# DingDong.net
KiCad netlist of a schematic drawn in Altium Designer
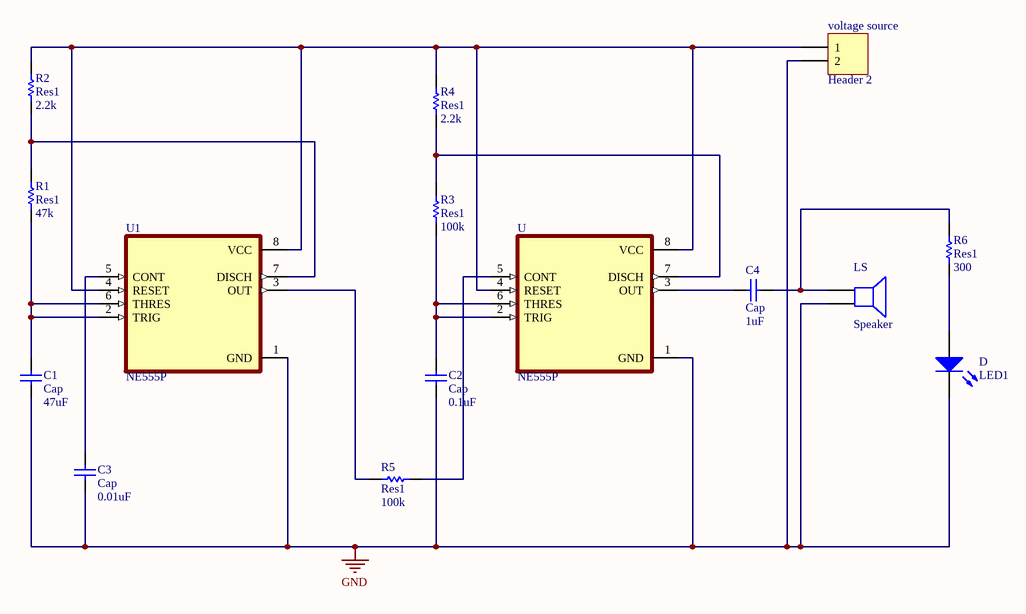
[diagram p0: DingDong.SchDoc]

(export (version "E")
  (design (tool "Eeschema 10.0.6"))
  (components
    (comp (ref "C1")
      (value "Cap")
      (footprint "RAD-0.3")
      (description "Capacitor")
      (fields (field (name "ALTIUM_VALUE") "47uF") (field (name "PUBLISHER") "Altium Limited"))
      (libsource (lib "Miscellaneous Devices") (part "Cap"))
    )
    (comp (ref "C2")
      (value "Cap")
      (footprint "RAD-0.3")
      (description "Capacitor")
      (fields (field (name "ALTIUM_VALUE") "0.1uF") (field (name "PUBLISHER") "Altium Limited"))
      (libsource (lib "Miscellaneous Devices") (part "Cap"))
    )
    (comp (ref "C3")
      (value "Cap")
      (footprint "RAD-0.3")
      (description "Capacitor")
      (fields (field (name "ALTIUM_VALUE") "0.01uF") (field (name "PUBLISHER") "Altium Limited"))
      (libsource (lib "Miscellaneous Devices") (part "Cap"))
    )
    (comp (ref "C4")
      (value "Cap")
      (footprint "RAD-0.3")
      (description "Capacitor")
      (fields (field (name "ALTIUM_VALUE") "1uF") (field (name "PUBLISHER") "Altium Limited"))
      (libsource (lib "Miscellaneous Devices") (part "Cap"))
    )
    (comp (ref "D")
      (value "LED1")
      (footprint "LED-1")
      (description "Typical RED GaAs LED")
      (fields (field (name "PUBLISHER") "Altium Limited"))
      (libsource (lib "Miscellaneous Devices") (part "LED1"))
    )
    (comp (ref "LS")
      (value "Speaker")
      (footprint "PIN2")
      (description "Loudspeaker")
      (fields (field (name "PUBLISHER") "Altium Limited"))
      (libsource (lib "Miscellaneous Devices") (part "Speaker"))
    )
    (comp (ref "R1")
      (value "Res1")
      (footprint "AXIAL-0.3")
      (description "Resistor")
      (fields (field (name "ALTIUM_VALUE") "47k") (field (name "PUBLISHER") "Altium Limited"))
      (libsource (lib "Miscellaneous Devices") (part "Res1"))
    )
    (comp (ref "R2")
      (value "Res1")
      (footprint "AXIAL-0.3")
      (description "Resistor")
      (fields (field (name "ALTIUM_VALUE") "2.2k") (field (name "PUBLISHER") "Altium Limited"))
      (libsource (lib "Miscellaneous Devices") (part "Res1"))
    )
    (comp (ref "R3")
      (value "Res1")
      (footprint "AXIAL-0.3")
      (description "Resistor")
      (fields (field (name "ALTIUM_VALUE") "100k") (field (name "PUBLISHER") "Altium Limited"))
      (libsource (lib "Miscellaneous Devices") (part "Res1"))
    )
    (comp (ref "R4")
      (value "Res1")
      (footprint "AXIAL-0.3")
      (description "Resistor")
      (fields (field (name "ALTIUM_VALUE") "2.2k") (field (name "PUBLISHER") "Altium Limited"))
      (libsource (lib "Miscellaneous Devices") (part "Res1"))
    )
    (comp (ref "R5")
      (value "Res1")
      (footprint "AXIAL-0.3")
      (description "Resistor")
      (fields (field (name "ALTIUM_VALUE") "100k") (field (name "PUBLISHER") "Altium Limited"))
      (libsource (lib "Miscellaneous Devices") (part "Res1"))
    )
    (comp (ref "R6")
      (value "Res1")
      (footprint "AXIAL-0.3")
      (description "Resistor")
      (fields (field (name "ALTIUM_VALUE") "300") (field (name "PUBLISHER") "Altium Limited"))
      (libsource (lib "Miscellaneous Devices") (part "Res1"))
    )
    (comp (ref "U")
      (value "NE555P")
      (footprint "DIP794W45P254L959H508Q8")
      (description "Single Precision Timer")
      (fields (field (name "MF") "Texas Instruments"))
      (libsource (lib "NE555P") (part "NE555P"))
    )
    (comp (ref "U1")
      (value "NE555P")
      (footprint "DIP794W45P254L959H508Q8")
      (description "Single Precision Timer")
      (fields (field (name "MF") "Texas Instruments"))
      (libsource (lib "NE555P") (part "NE555P"))
    )
    (comp (ref "voltage source")
      (value "Header 2")
      (footprint "HDR1X2")
      (description "Header, 2-Pin")
      (fields (field (name "PUBLISHER") "Altium Limited"))
      (libsource (lib "Miscellaneous Connectors") (part "Header 2"))
    )
  )
  (nets
    (net (code "1") (name "GND") (class "Default")
      (node (ref "C1") (pin "1") (pinfunction "1_1") (pintype "passive"))
      (node (ref "C2") (pin "1") (pinfunction "1_1") (pintype "passive"))
      (node (ref "C3") (pin "1") (pinfunction "1_1") (pintype "passive"))
      (node (ref "D") (pin "2") (pinfunction "K_2") (pintype "passive"))
      (node (ref "LS") (pin "2") (pinfunction "2_2") (pintype "passive"))
      (node (ref "U") (pin "1") (pinfunction "GND_1") (pintype "power_in"))
      (node (ref "U1") (pin "1") (pinfunction "GND_1") (pintype "power_in"))
      (node (ref "voltage source") (pin "2") (pinfunction "2_2") (pintype "passive"))
    )
    (net (code "2") (name "Net-(C4-Pad2)") (class "Default")
      (node (ref "C4") (pin "2") (pinfunction "2_2") (pintype "passive"))
      (node (ref "LS") (pin "1") (pinfunction "1_1") (pintype "passive"))
      (node (ref "R6") (pin "2") (pinfunction "2_2") (pintype "passive"))
    )
    (net (code "3") (name "Net-(D-A)") (class "Default")
      (node (ref "D") (pin "1") (pinfunction "A_1") (pintype "passive"))
      (node (ref "R6") (pin "1") (pinfunction "1_1") (pintype "passive"))
    )
    (net (code "4") (name "Net-(U-CONT)") (class "Default")
      (node (ref "R5") (pin "2") (pinfunction "2_2") (pintype "passive"))
      (node (ref "U") (pin "5") (pinfunction "CONT_5") (pintype "input"))
    )
    (net (code "5") (name "Net-(U-DISCH)") (class "Default")
      (node (ref "R3") (pin "2") (pinfunction "2_2") (pintype "passive"))
      (node (ref "R4") (pin "1") (pinfunction "1_1") (pintype "passive"))
      (node (ref "U") (pin "7") (pinfunction "DISCH_7") (pintype "output"))
    )
    (net (code "6") (name "Net-(U-OUT)") (class "Default")
      (node (ref "C4") (pin "1") (pinfunction "1_1") (pintype "passive"))
      (node (ref "U") (pin "3") (pinfunction "OUT_3") (pintype "output"))
    )
    (net (code "7") (name "Net-(U-RESET)") (class "Default")
      (node (ref "R2") (pin "2") (pinfunction "2_2") (pintype "passive"))
      (node (ref "R4") (pin "2") (pinfunction "2_2") (pintype "passive"))
      (node (ref "U") (pin "4") (pinfunction "RESET_4") (pintype "input"))
      (node (ref "U") (pin "8") (pinfunction "VCC_8") (pintype "power_in"))
      (node (ref "U1") (pin "4") (pinfunction "RESET_4") (pintype "input"))
      (node (ref "U1") (pin "8") (pinfunction "VCC_8") (pintype "power_in"))
      (node (ref "voltage source") (pin "1") (pinfunction "1_1") (pintype "passive"))
    )
    (net (code "8") (name "Net-(U-THRES)") (class "Default")
      (node (ref "C2") (pin "2") (pinfunction "2_2") (pintype "passive"))
      (node (ref "R3") (pin "1") (pinfunction "1_1") (pintype "passive"))
      (node (ref "U") (pin "2") (pinfunction "TRIG_2") (pintype "input"))
      (node (ref "U") (pin "6") (pinfunction "THRES_6") (pintype "input"))
    )
    (net (code "9") (name "Net-(U1-CONT)") (class "Default")
      (node (ref "C3") (pin "2") (pinfunction "2_2") (pintype "passive"))
      (node (ref "U1") (pin "5") (pinfunction "CONT_5") (pintype "input"))
    )
    (net (code "10") (name "Net-(U1-DISCH)") (class "Default")
      (node (ref "R1") (pin "2") (pinfunction "2_2") (pintype "passive"))
      (node (ref "R2") (pin "1") (pinfunction "1_1") (pintype "passive"))
      (node (ref "U1") (pin "7") (pinfunction "DISCH_7") (pintype "output"))
    )
    (net (code "11") (name "Net-(U1-OUT)") (class "Default")
      (node (ref "R5") (pin "1") (pinfunction "1_1") (pintype "passive"))
      (node (ref "U1") (pin "3") (pinfunction "OUT_3") (pintype "output"))
    )
    (net (code "12") (name "Net-(U1-THRES)") (class "Default")
      (node (ref "C1") (pin "2") (pinfunction "2_2") (pintype "passive"))
      (node (ref "R1") (pin "1") (pinfunction "1_1") (pintype "passive"))
      (node (ref "U1") (pin "2") (pinfunction "TRIG_2") (pintype "input"))
      (node (ref "U1") (pin "6") (pinfunction "THRES_6") (pintype "input"))
    )
  )
)
